# Oscilador_555_r00.net
KiCad netlist of a schematic drawn in EAGLE
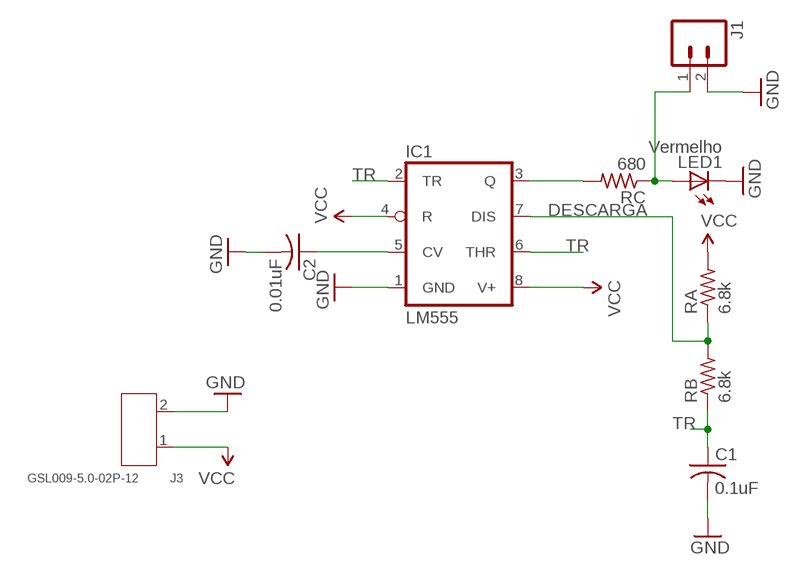
[diagram p0: schematic, sheet 1]

(export (version "E")
  (design (tool "Eeschema 10.0.6"))
  (components
    (comp (ref "C1")
      (value "0.1uF")
      (footprint "eagle-import:C050-024X044")
      (libsource (lib "eagle-import") (part "C-US050-024X044"))
    )
    (comp (ref "C2")
      (value "0.01uF")
      (footprint "eagle-import:C050-024X044")
      (libsource (lib "eagle-import") (part "C-US050-024X044"))
    )
    (comp (ref "IC1")
      (value "LM555")
      (footprint "eagle-import:DIL08-ROUND")
      (libsource (lib "eagle-import") (part "555NLM"))
    )
    (comp (ref "J1")
      (value "M02PTH")
      (footprint "eagle-import:1X02")
      (libsource (lib "eagle-import") (part "M02PTH"))
    )
    (comp (ref "J3")
      (value "GSL009-5.0-02P-12")
      (footprint "eagle-import:H2-5.0-10.5X8.0MM")
      (libsource (lib "eagle-import") (part "SCREW-TERMINAL-BLUE(2P-5.0)"))
    )
    (comp (ref "LED1")
      (value "Vermelho")
      (footprint "eagle-import:LED5MM")
      (libsource (lib "eagle-import") (part "LED5MM"))
    )
    (comp (ref "RA")
      (value "6.8k")
      (footprint "eagle-import:0207_10")
      (libsource (lib "eagle-import") (part "R-US_0207/10"))
    )
    (comp (ref "RB")
      (value "6.8k")
      (footprint "eagle-import:0207_10")
      (libsource (lib "eagle-import") (part "R-US_0207/10"))
    )
    (comp (ref "RC")
      (value "680")
      (footprint "eagle-import:0207_10")
      (libsource (lib "eagle-import") (part "R-US_0207/10"))
    )
  )
  (nets
    (net (code "1") (name "/DESCARGA") (class "Default")
      (node (ref "IC1") (pin "7") (pinfunction "DIS_7") (pintype "input"))
      (node (ref "RA") (pin "1") (pinfunction "1_1") (pintype "passive"))
      (node (ref "RB") (pin "2") (pinfunction "2_2") (pintype "passive"))
    )
    (net (code "2") (name "/TR") (class "Default")
      (node (ref "C1") (pin "1") (pinfunction "1_1") (pintype "passive"))
      (node (ref "IC1") (pin "2") (pinfunction "TR_2") (pintype "input"))
      (node (ref "IC1") (pin "6") (pinfunction "THR_6") (pintype "input"))
      (node (ref "RB") (pin "1") (pinfunction "1_1") (pintype "passive"))
    )
    (net (code "3") (name "GND") (class "Default")
      (node (ref "C1") (pin "2") (pinfunction "2_2") (pintype "passive"))
      (node (ref "C2") (pin "2") (pinfunction "2_2") (pintype "passive"))
      (node (ref "IC1") (pin "1") (pinfunction "GND_1") (pintype "power_in"))
      (node (ref "J1") (pin "2") (pinfunction "2_2") (pintype "passive"))
      (node (ref "J3") (pin "2") (pinfunction "2_2") (pintype "bidirectional"))
      (node (ref "LED1") (pin "K") (pinfunction "C_K") (pintype "passive"))
    )
    (net (code "4") (name "Net-(IC1-CV)") (class "Default")
      (node (ref "C2") (pin "1") (pinfunction "1_1") (pintype "passive"))
      (node (ref "IC1") (pin "5") (pinfunction "CV_5") (pintype "input"))
    )
    (net (code "5") (name "Net-(IC1-Q)") (class "Default")
      (node (ref "IC1") (pin "3") (pinfunction "Q_3") (pintype "output"))
      (node (ref "RC") (pin "2") (pinfunction "2_2") (pintype "passive"))
    )
    (net (code "6") (name "Net-(J1-Pad1)") (class "Default")
      (node (ref "J1") (pin "1") (pinfunction "1_1") (pintype "passive"))
      (node (ref "LED1") (pin "A") (pinfunction "A_A") (pintype "passive"))
      (node (ref "RC") (pin "1") (pinfunction "1_1") (pintype "passive"))
    )
    (net (code "7") (name "VCC") (class "Default")
      (node (ref "IC1") (pin "4") (pinfunction "R_4") (pintype "input"))
      (node (ref "IC1") (pin "8") (pinfunction "V+_8") (pintype "power_in"))
      (node (ref "J3") (pin "1") (pinfunction "1_1") (pintype "bidirectional"))
      (node (ref "RA") (pin "2") (pinfunction "2_2") (pintype "passive"))
    )
  )
)
